# In-Out.net
KiCad netlist of a schematic drawn in Altium Designer
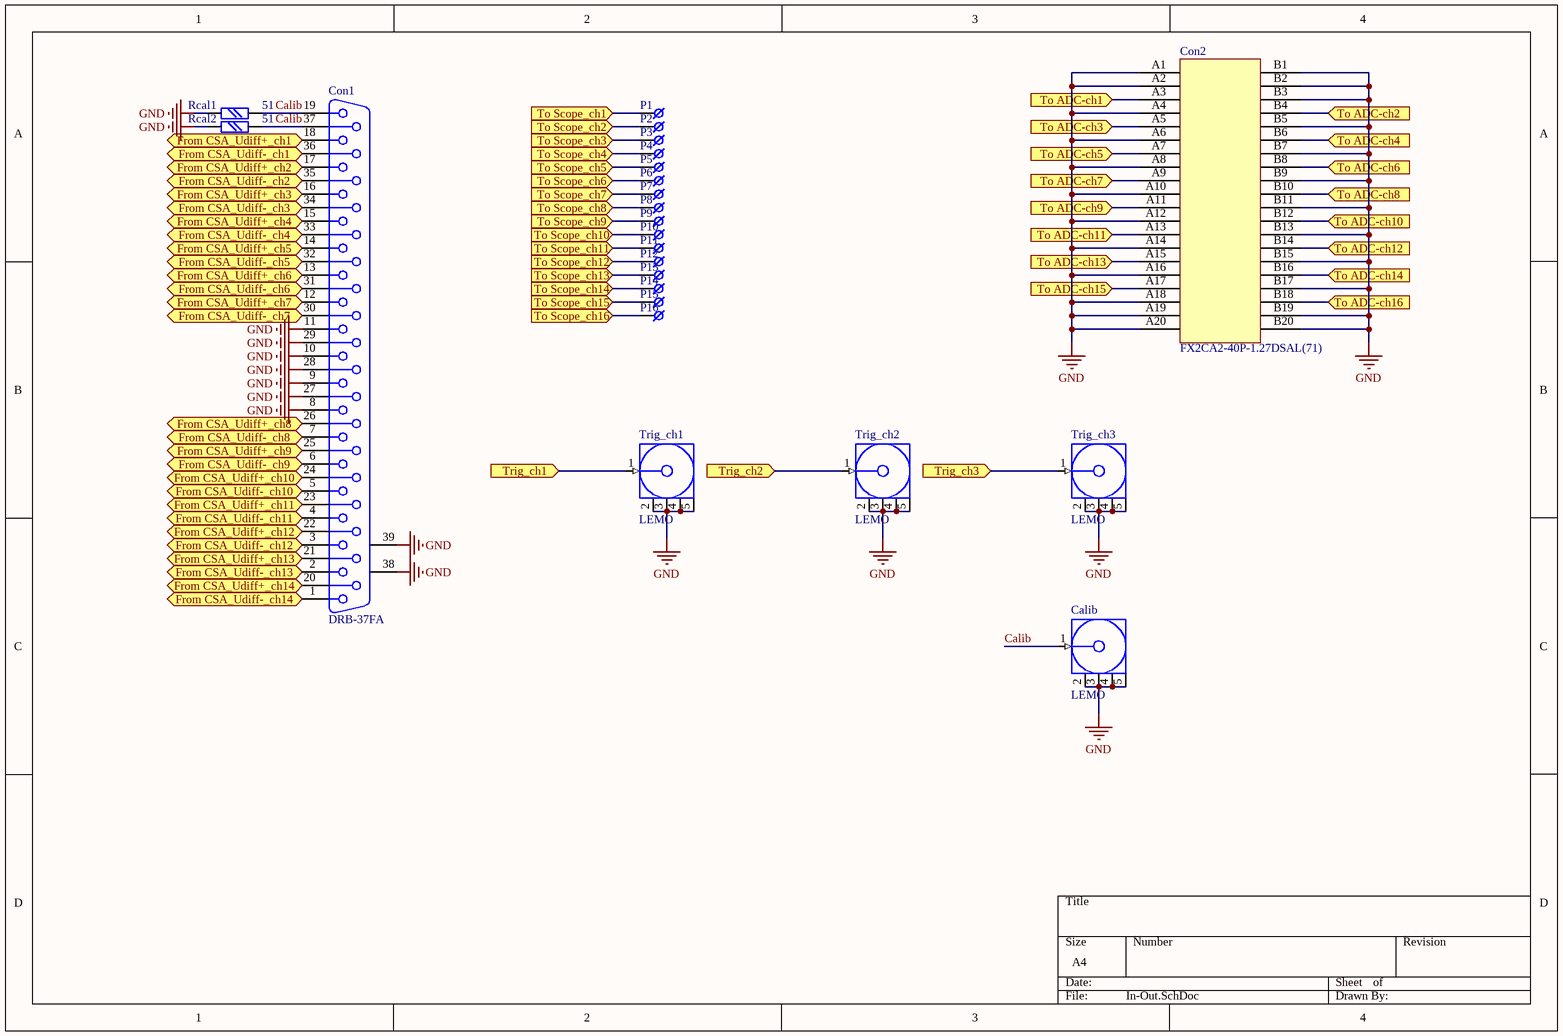
[diagram p0: In-Out.SchDoc]

(export (version "E")
  (design (tool "Eeschema 10.0.6"))
  (components
    (comp (ref "Calib")
      (value "LEMO")
      (footprint "LEMO")
      (fields (field (name "PUBLISHER") "Altium Limited"))
      (libsource (lib "Miscellaneous Connectors") (part "COAX-F"))
    )
    (comp (ref "Con1") (value "DRB-37FA") (footprint "DBR-F-37") (libsource (lib "vDevice") (part "DBR-37F")))
    (comp (ref "Con2")
      (value "FX2CA2-40P-1.27DSAL(71)")
      (libsource (lib "vDevice") (part "FX2CA2-40P-1.27DSAL(71)"))
    )
    (comp (ref "P1") (value "KLEMME") (footprint "Pad12") (libsource (lib "vDevice") (part "KLEMME")))
    (comp (ref "P2") (value "KLEMME") (footprint "Pad12") (libsource (lib "vDevice") (part "KLEMME")))
    (comp (ref "P3") (value "KLEMME") (footprint "Pad12") (libsource (lib "vDevice") (part "KLEMME")))
    (comp (ref "P4") (value "KLEMME") (footprint "Pad12") (libsource (lib "vDevice") (part "KLEMME")))
    (comp (ref "P5") (value "KLEMME") (footprint "Pad12") (libsource (lib "vDevice") (part "KLEMME")))
    (comp (ref "P6") (value "KLEMME") (footprint "Pad12") (libsource (lib "vDevice") (part "KLEMME")))
    (comp (ref "P7") (value "KLEMME") (footprint "Pad12") (libsource (lib "vDevice") (part "KLEMME")))
    (comp (ref "P8") (value "KLEMME") (footprint "Pad12") (libsource (lib "vDevice") (part "KLEMME")))
    (comp (ref "P9") (value "KLEMME") (footprint "Pad12") (libsource (lib "vDevice") (part "KLEMME")))
    (comp (ref "P10") (value "KLEMME") (footprint "Pad12") (libsource (lib "vDevice") (part "KLEMME")))
    (comp (ref "P11") (value "KLEMME") (footprint "Pad12") (libsource (lib "vDevice") (part "KLEMME")))
    (comp (ref "P12") (value "KLEMME") (footprint "Pad12") (libsource (lib "vDevice") (part "KLEMME")))
    (comp (ref "P13") (value "KLEMME") (footprint "Pad12") (libsource (lib "vDevice") (part "KLEMME")))
    (comp (ref "P14") (value "KLEMME") (footprint "Pad12") (libsource (lib "vDevice") (part "KLEMME")))
    (comp (ref "P15") (value "KLEMME") (footprint "Pad12") (libsource (lib "vDevice") (part "KLEMME")))
    (comp (ref "P16") (value "KLEMME") (footprint "Pad12") (libsource (lib "vDevice") (part "KLEMME")))
    (comp (ref "Rcal1") (value "51") (footprint "chip0603") (libsource (lib "vDevice") (part "R")))
    (comp (ref "Rcal2") (value "51") (footprint "chip0603") (libsource (lib "vDevice") (part "R")))
    (comp (ref "Trig_ch1")
      (value "LEMO")
      (footprint "LEMO")
      (fields (field (name "PUBLISHER") "Altium Limited"))
      (libsource (lib "Miscellaneous Connectors") (part "COAX-F"))
    )
    (comp (ref "Trig_ch2")
      (value "LEMO")
      (footprint "LEMO")
      (fields (field (name "PUBLISHER") "Altium Limited"))
      (libsource (lib "Miscellaneous Connectors") (part "COAX-F"))
    )
    (comp (ref "Trig_ch3")
      (value "LEMO")
      (footprint "LEMO")
      (fields (field (name "PUBLISHER") "Altium Limited"))
      (libsource (lib "Miscellaneous Connectors") (part "COAX-F"))
    )
  )
  (nets
    (net (code "1") (name "/Calib") (class "Default")
      (node (ref "Calib") (pin "1") (pinfunction "Signal_1") (pintype "input"))
      (node (ref "Con1") (pin "19") (pinfunction "19_19") (pintype "passive"))
      (node (ref "Con1") (pin "37") (pinfunction "37_37") (pintype "passive"))
      (node (ref "Rcal1") (pin "1") (pinfunction "1_1") (pintype "passive"))
      (node (ref "Rcal2") (pin "1") (pinfunction "1_1") (pintype "passive"))
    )
    (net (code "2") (name "/From CSA_Udiff+_ch1") (class "Default")
      (node (ref "Con1") (pin "18") (pinfunction "18_18") (pintype "passive"))
    )
    (net (code "3") (name "/From CSA_Udiff+_ch2") (class "Default")
      (node (ref "Con1") (pin "17") (pinfunction "17_17") (pintype "passive"))
    )
    (net (code "4") (name "/From CSA_Udiff+_ch3") (class "Default")
      (node (ref "Con1") (pin "16") (pinfunction "16_16") (pintype "passive"))
    )
    (net (code "5") (name "/From CSA_Udiff+_ch4") (class "Default")
      (node (ref "Con1") (pin "15") (pinfunction "15_15") (pintype "passive"))
    )
    (net (code "6") (name "/From CSA_Udiff+_ch5") (class "Default")
      (node (ref "Con1") (pin "14") (pinfunction "14_14") (pintype "passive"))
    )
    (net (code "7") (name "/From CSA_Udiff+_ch6") (class "Default")
      (node (ref "Con1") (pin "13") (pinfunction "13_13") (pintype "passive"))
    )
    (net (code "8") (name "/From CSA_Udiff+_ch7") (class "Default")
      (node (ref "Con1") (pin "12") (pinfunction "12_12") (pintype "passive"))
    )
    (net (code "9") (name "/From CSA_Udiff+_ch8") (class "Default")
      (node (ref "Con1") (pin "26") (pinfunction "26_26") (pintype "passive"))
    )
    (net (code "10") (name "/From CSA_Udiff+_ch9") (class "Default")
      (node (ref "Con1") (pin "25") (pinfunction "25_25") (pintype "passive"))
    )
    (net (code "11") (name "/From CSA_Udiff+_ch10") (class "Default")
      (node (ref "Con1") (pin "24") (pinfunction "24_24") (pintype "passive"))
    )
    (net (code "12") (name "/From CSA_Udiff+_ch11") (class "Default")
      (node (ref "Con1") (pin "23") (pinfunction "23_23") (pintype "passive"))
    )
    (net (code "13") (name "/From CSA_Udiff+_ch12") (class "Default")
      (node (ref "Con1") (pin "22") (pinfunction "22_22") (pintype "passive"))
    )
    (net (code "14") (name "/From CSA_Udiff+_ch13") (class "Default")
      (node (ref "Con1") (pin "21") (pinfunction "21_21") (pintype "passive"))
    )
    (net (code "15") (name "/From CSA_Udiff+_ch14") (class "Default")
      (node (ref "Con1") (pin "20") (pinfunction "20_20") (pintype "passive"))
    )
    (net (code "16") (name "/From CSA_Udiff-_ch1") (class "Default")
      (node (ref "Con1") (pin "36") (pinfunction "36_36") (pintype "passive"))
    )
    (net (code "17") (name "/From CSA_Udiff-_ch2") (class "Default")
      (node (ref "Con1") (pin "35") (pinfunction "35_35") (pintype "passive"))
    )
    (net (code "18") (name "/From CSA_Udiff-_ch3") (class "Default")
      (node (ref "Con1") (pin "34") (pinfunction "34_34") (pintype "passive"))
    )
    (net (code "19") (name "/From CSA_Udiff-_ch4") (class "Default")
      (node (ref "Con1") (pin "33") (pinfunction "33_33") (pintype "passive"))
    )
    (net (code "20") (name "/From CSA_Udiff-_ch5") (class "Default")
      (node (ref "Con1") (pin "32") (pinfunction "32_32") (pintype "passive"))
    )
    (net (code "21") (name "/From CSA_Udiff-_ch6") (class "Default")
      (node (ref "Con1") (pin "31") (pinfunction "31_31") (pintype "passive"))
    )
    (net (code "22") (name "/From CSA_Udiff-_ch7") (class "Default")
      (node (ref "Con1") (pin "30") (pinfunction "30_30") (pintype "passive"))
    )
    (net (code "23") (name "/From CSA_Udiff-_ch8") (class "Default")
      (node (ref "Con1") (pin "7") (pinfunction "7_7") (pintype "passive"))
    )
    (net (code "24") (name "/From CSA_Udiff-_ch9") (class "Default")
      (node (ref "Con1") (pin "6") (pinfunction "6_6") (pintype "passive"))
    )
    (net (code "25") (name "/From CSA_Udiff-_ch10") (class "Default")
      (node (ref "Con1") (pin "5") (pinfunction "5_5") (pintype "passive"))
    )
    (net (code "26") (name "/From CSA_Udiff-_ch11") (class "Default")
      (node (ref "Con1") (pin "4") (pinfunction "4_4") (pintype "passive"))
    )
    (net (code "27") (name "/From CSA_Udiff-_ch12") (class "Default")
      (node (ref "Con1") (pin "3") (pinfunction "3_3") (pintype "passive"))
    )
    (net (code "28") (name "/From CSA_Udiff-_ch13") (class "Default")
      (node (ref "Con1") (pin "2") (pinfunction "2_2") (pintype "passive"))
    )
    (net (code "29") (name "/From CSA_Udiff-_ch14") (class "Default")
      (node (ref "Con1") (pin "1") (pinfunction "1_1") (pintype "passive"))
    )
    (net (code "30") (name "/To ADC-ch1") (class "Default")
      (node (ref "Con2") (pin "A3") (pinfunction "3_A3") (pintype "passive"))
    )
    (net (code "31") (name "/To ADC-ch2") (class "Default")
      (node (ref "Con2") (pin "B4") (pinfunction "4_B4") (pintype "passive"))
    )
    (net (code "32") (name "/To ADC-ch3") (class "Default")
      (node (ref "Con2") (pin "A5") (pinfunction "5_A5") (pintype "passive"))
    )
    (net (code "33") (name "/To ADC-ch4") (class "Default")
      (node (ref "Con2") (pin "B6") (pinfunction "6_B6") (pintype "passive"))
    )
    (net (code "34") (name "/To ADC-ch5") (class "Default")
      (node (ref "Con2") (pin "A7") (pinfunction "7_A7") (pintype "passive"))
    )
    (net (code "35") (name "/To ADC-ch6") (class "Default")
      (node (ref "Con2") (pin "B8") (pinfunction "8_B8") (pintype "passive"))
    )
    (net (code "36") (name "/To ADC-ch7") (class "Default")
      (node (ref "Con2") (pin "A9") (pinfunction "9_A9") (pintype "passive"))
    )
    (net (code "37") (name "/To ADC-ch8") (class "Default")
      (node (ref "Con2") (pin "B10") (pinfunction "10_B10") (pintype "passive"))
    )
    (net (code "38") (name "/To ADC-ch9") (class "Default")
      (node (ref "Con2") (pin "A11") (pinfunction "11_A11") (pintype "passive"))
    )
    (net (code "39") (name "/To ADC-ch10") (class "Default")
      (node (ref "Con2") (pin "B12") (pinfunction "12_B12") (pintype "passive"))
    )
    (net (code "40") (name "/To ADC-ch11") (class "Default")
      (node (ref "Con2") (pin "A13") (pinfunction "13_A13") (pintype "passive"))
    )
    (net (code "41") (name "/To ADC-ch12") (class "Default")
      (node (ref "Con2") (pin "B14") (pinfunction "14_B14") (pintype "passive"))
    )
    (net (code "42") (name "/To ADC-ch13") (class "Default")
      (node (ref "Con2") (pin "A15") (pinfunction "15_A15") (pintype "passive"))
    )
    (net (code "43") (name "/To ADC-ch14") (class "Default")
      (node (ref "Con2") (pin "B16") (pinfunction "16_B16") (pintype "passive"))
    )
    (net (code "44") (name "/To ADC-ch15") (class "Default")
      (node (ref "Con2") (pin "A17") (pinfunction "17_A17") (pintype "passive"))
    )
    (net (code "45") (name "/To ADC-ch16") (class "Default")
      (node (ref "Con2") (pin "B18") (pinfunction "18_B18") (pintype "passive"))
    )
    (net (code "46") (name "/To Scope_ch1") (class "Default")
      (node (ref "P1") (pin "PAD") (pinfunction "PAD_PAD") (pintype "passive"))
    )
    (net (code "47") (name "/To Scope_ch2") (class "Default")
      (node (ref "P2") (pin "PAD") (pinfunction "PAD_PAD") (pintype "passive"))
    )
    (net (code "48") (name "/To Scope_ch3") (class "Default")
      (node (ref "P3") (pin "PAD") (pinfunction "PAD_PAD") (pintype "passive"))
    )
    (net (code "49") (name "/To Scope_ch4") (class "Default")
      (node (ref "P4") (pin "PAD") (pinfunction "PAD_PAD") (pintype "passive"))
    )
    (net (code "50") (name "/To Scope_ch5") (class "Default")
      (node (ref "P5") (pin "PAD") (pinfunction "PAD_PAD") (pintype "passive"))
    )
    (net (code "51") (name "/To Scope_ch6") (class "Default")
      (node (ref "P6") (pin "PAD") (pinfunction "PAD_PAD") (pintype "passive"))
    )
    (net (code "52") (name "/To Scope_ch7") (class "Default")
      (node (ref "P7") (pin "PAD") (pinfunction "PAD_PAD") (pintype "passive"))
    )
    (net (code "53") (name "/To Scope_ch8") (class "Default")
      (node (ref "P8") (pin "PAD") (pinfunction "PAD_PAD") (pintype "passive"))
    )
    (net (code "54") (name "/To Scope_ch9") (class "Default")
      (node (ref "P9") (pin "PAD") (pinfunction "PAD_PAD") (pintype "passive"))
    )
    (net (code "55") (name "/To Scope_ch10") (class "Default")
      (node (ref "P10") (pin "PAD") (pinfunction "PAD_PAD") (pintype "passive"))
    )
    (net (code "56") (name "/To Scope_ch11") (class "Default")
      (node (ref "P11") (pin "PAD") (pinfunction "PAD_PAD") (pintype "passive"))
    )
    (net (code "57") (name "/To Scope_ch12") (class "Default")
      (node (ref "P12") (pin "PAD") (pinfunction "PAD_PAD") (pintype "passive"))
    )
    (net (code "58") (name "/To Scope_ch13") (class "Default")
      (node (ref "P13") (pin "PAD") (pinfunction "PAD_PAD") (pintype "passive"))
    )
    (net (code "59") (name "/To Scope_ch14") (class "Default")
      (node (ref "P14") (pin "PAD") (pinfunction "PAD_PAD") (pintype "passive"))
    )
    (net (code "60") (name "/To Scope_ch15") (class "Default")
      (node (ref "P15") (pin "PAD") (pinfunction "PAD_PAD") (pintype "passive"))
    )
    (net (code "61") (name "/To Scope_ch16") (class "Default")
      (node (ref "P16") (pin "PAD") (pinfunction "PAD_PAD") (pintype "passive"))
    )
    (net (code "62") (name "/Trig_ch1") (class "Default")
      (node (ref "Trig_ch1") (pin "1") (pinfunction "Signal_1") (pintype "input"))
    )
    (net (code "63") (name "/Trig_ch2") (class "Default")
      (node (ref "Trig_ch2") (pin "1") (pinfunction "Signal_1") (pintype "input"))
    )
    (net (code "64") (name "/Trig_ch3") (class "Default")
      (node (ref "Trig_ch3") (pin "1") (pinfunction "Signal_1") (pintype "input"))
    )
    (net (code "65") (name "GND") (class "Default")
      (node (ref "Calib") (pin "2") (pinfunction "GND_2") (pintype "power_in"))
      (node (ref "Calib") (pin "3") (pinfunction "GND_3") (pintype "power_in"))
      (node (ref "Calib") (pin "4") (pinfunction "GND_4") (pintype "power_in"))
      (node (ref "Calib") (pin "5") (pinfunction "GND_5") (pintype "power_in"))
      (node (ref "Con1") (pin "10") (pinfunction "10_10") (pintype "passive"))
      (node (ref "Con1") (pin "11") (pinfunction "11_11") (pintype "passive"))
      (node (ref "Con1") (pin "27") (pinfunction "27_27") (pintype "passive"))
      (node (ref "Con1") (pin "28") (pinfunction "28_28") (pintype "passive"))
      (node (ref "Con1") (pin "29") (pinfunction "29_29") (pintype "passive"))
      (node (ref "Con1") (pin "38") (pinfunction "38_38") (pintype "passive"))
      (node (ref "Con1") (pin "39") (pinfunction "39_39") (pintype "passive"))
      (node (ref "Con1") (pin "8") (pinfunction "8_8") (pintype "passive"))
      (node (ref "Con1") (pin "9") (pinfunction "9_9") (pintype "passive"))
      (node (ref "Con2") (pin "A1") (pinfunction "1_A1") (pintype "passive"))
      (node (ref "Con2") (pin "A10") (pinfunction "10_A10") (pintype "passive"))
      (node (ref "Con2") (pin "A12") (pinfunction "12_A12") (pintype "passive"))
      (node (ref "Con2") (pin "A14") (pinfunction "14_A14") (pintype "passive"))
      (node (ref "Con2") (pin "A16") (pinfunction "16_A16") (pintype "passive"))
      (node (ref "Con2") (pin "A18") (pinfunction "18_A18") (pintype "passive"))
      (node (ref "Con2") (pin "A19") (pinfunction "19_A19") (pintype "passive"))
      (node (ref "Con2") (pin "A2") (pinfunction "2_A2") (pintype "passive"))
      (node (ref "Con2") (pin "A20") (pinfunction "20_A20") (pintype "passive"))
      (node (ref "Con2") (pin "A4") (pinfunction "4_A4") (pintype "passive"))
      (node (ref "Con2") (pin "A6") (pinfunction "6_A6") (pintype "passive"))
      (node (ref "Con2") (pin "A8") (pinfunction "8_A8") (pintype "passive"))
      (node (ref "Con2") (pin "B1") (pinfunction "1_B1") (pintype "passive"))
      (node (ref "Con2") (pin "B11") (pinfunction "11_B11") (pintype "passive"))
      (node (ref "Con2") (pin "B13") (pinfunction "13_B13") (pintype "passive"))
      (node (ref "Con2") (pin "B15") (pinfunction "15_B15") (pintype "passive"))
      (node (ref "Con2") (pin "B17") (pinfunction "17_B17") (pintype "passive"))
      (node (ref "Con2") (pin "B19") (pinfunction "19_B19") (pintype "passive"))
      (node (ref "Con2") (pin "B2") (pinfunction "2_B2") (pintype "passive"))
      (node (ref "Con2") (pin "B20") (pinfunction "20_B20") (pintype "passive"))
      (node (ref "Con2") (pin "B3") (pinfunction "3_B3") (pintype "passive"))
      (node (ref "Con2") (pin "B5") (pinfunction "5_B5") (pintype "passive"))
      (node (ref "Con2") (pin "B7") (pinfunction "7_B7") (pintype "passive"))
      (node (ref "Con2") (pin "B9") (pinfunction "9_B9") (pintype "passive"))
      (node (ref "Rcal1") (pin "2") (pinfunction "2_2") (pintype "passive"))
      (node (ref "Rcal2") (pin "2") (pinfunction "2_2") (pintype "passive"))
      (node (ref "Trig_ch1") (pin "2") (pinfunction "GND_2") (pintype "power_in"))
      (node (ref "Trig_ch1") (pin "3") (pinfunction "GND_3") (pintype "power_in"))
      (node (ref "Trig_ch1") (pin "4") (pinfunction "GND_4") (pintype "power_in"))
      (node (ref "Trig_ch1") (pin "5") (pinfunction "GND_5") (pintype "power_in"))
      (node (ref "Trig_ch2") (pin "2") (pinfunction "GND_2") (pintype "power_in"))
      (node (ref "Trig_ch2") (pin "3") (pinfunction "GND_3") (pintype "power_in"))
      (node (ref "Trig_ch2") (pin "4") (pinfunction "GND_4") (pintype "power_in"))
      (node (ref "Trig_ch2") (pin "5") (pinfunction "GND_5") (pintype "power_in"))
      (node (ref "Trig_ch3") (pin "2") (pinfunction "GND_2") (pintype "power_in"))
      (node (ref "Trig_ch3") (pin "3") (pinfunction "GND_3") (pintype "power_in"))
      (node (ref "Trig_ch3") (pin "4") (pinfunction "GND_4") (pintype "power_in"))
      (node (ref "Trig_ch3") (pin "5") (pinfunction "GND_5") (pintype "power_in"))
    )
  )
)
